# DCDC_Motherbord.net
KiCad netlist of a schematic drawn in Altium Designer
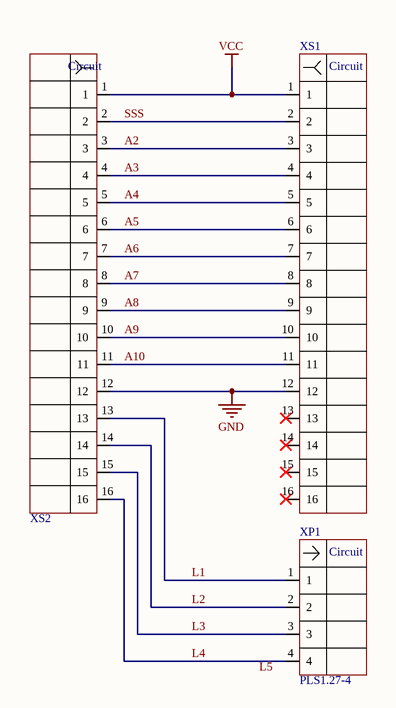
[diagram p0: DCDC_Motherbord.SchDoc]

(export (version "E")
  (design (tool "Eeschema 10.0.6"))
  (components
    (comp (ref "XP1")
      (value "PLS1.27-4")
      (footprint "PLLS1.27-4")
      (libsource (lib "SssAccesDatbase") (part "XP-4"))
    )
    (comp (ref "XS1")
      (value "PBD-16")
      (footprint "PBD-16-3D")
      (description "CONN RCPT 16POS 0.1 GOLD PCB")
      (fields (field (name "PART NUMBER") "SH2-16G") (field (name "DIGI-KEY PART NUMBER") "ED3071-ND"))
      (libsource (lib "") (part "XS-16_1"))
    )
    (comp (ref "XS2")
      (value "PBD-16")
      (footprint "PBD-16-3D")
      (description "CONN RCPT 16POS 0.1 GOLD PCB")
      (fields (field (name "PART NUMBER") "SH2-16G") (field (name "DIGI-KEY PART NUMBER") "ED3071-ND"))
      (libsource (lib "SssAccesDatbase") (part "XS-16"))
    )
  )
  (nets
    (net (code "1") (name "/A2") (class "Default")
      (node (ref "XS1") (pin "3") (pinfunction "3_3") (pintype "passive"))
      (node (ref "XS2") (pin "3") (pinfunction "3_3") (pintype "passive"))
    )
    (net (code "2") (name "/A3") (class "Default")
      (node (ref "XS1") (pin "4") (pinfunction "4_4") (pintype "passive"))
      (node (ref "XS2") (pin "4") (pinfunction "4_4") (pintype "passive"))
    )
    (net (code "3") (name "/A4") (class "Default")
      (node (ref "XS1") (pin "5") (pinfunction "5_5") (pintype "passive"))
      (node (ref "XS2") (pin "5") (pinfunction "5_5") (pintype "passive"))
    )
    (net (code "4") (name "/A5") (class "Default")
      (node (ref "XS1") (pin "6") (pinfunction "6_6") (pintype "passive"))
      (node (ref "XS2") (pin "6") (pinfunction "6_6") (pintype "passive"))
    )
    (net (code "5") (name "/A6") (class "Default")
      (node (ref "XS1") (pin "7") (pinfunction "7_7") (pintype "passive"))
      (node (ref "XS2") (pin "7") (pinfunction "7_7") (pintype "passive"))
    )
    (net (code "6") (name "/A7") (class "Default")
      (node (ref "XS1") (pin "8") (pinfunction "8_8") (pintype "passive"))
      (node (ref "XS2") (pin "8") (pinfunction "8_8") (pintype "passive"))
    )
    (net (code "7") (name "/A8") (class "Default")
      (node (ref "XS1") (pin "9") (pinfunction "9_9") (pintype "passive"))
      (node (ref "XS2") (pin "9") (pinfunction "9_9") (pintype "passive"))
    )
    (net (code "8") (name "/A9") (class "Default")
      (node (ref "XS1") (pin "10") (pinfunction "10_10") (pintype "passive"))
      (node (ref "XS2") (pin "10") (pinfunction "10_10") (pintype "passive"))
    )
    (net (code "9") (name "/A10") (class "Default")
      (node (ref "XS1") (pin "11") (pinfunction "11_11") (pintype "passive"))
      (node (ref "XS2") (pin "11") (pinfunction "11_11") (pintype "passive"))
    )
    (net (code "10") (name "/L1") (class "Default")
      (node (ref "XP1") (pin "1") (pinfunction "1_1") (pintype "passive"))
      (node (ref "XS2") (pin "13") (pinfunction "13_13") (pintype "passive"))
    )
    (net (code "11") (name "/L2") (class "Default")
      (node (ref "XP1") (pin "2") (pinfunction "2_2") (pintype "passive"))
      (node (ref "XS2") (pin "14") (pinfunction "14_14") (pintype "passive"))
    )
    (net (code "12") (name "/L3") (class "Default")
      (node (ref "XP1") (pin "3") (pinfunction "3_3") (pintype "passive"))
      (node (ref "XS2") (pin "15") (pinfunction "15_15") (pintype "passive"))
    )
    (net (code "13") (name "/L4") (class "Default")
      (node (ref "XP1") (pin "4") (pinfunction "4_4") (pintype "passive"))
      (node (ref "XS2") (pin "16") (pinfunction "16_16") (pintype "passive"))
    )
    (net (code "15") (name "/SSS") (class "Default")
      (node (ref "XS1") (pin "2") (pinfunction "2_2") (pintype "passive"))
      (node (ref "XS2") (pin "2") (pinfunction "2_2") (pintype "passive"))
    )
    (net (code "16") (name "GND") (class "Default")
      (node (ref "XS1") (pin "12") (pinfunction "12_12") (pintype "passive"))
      (node (ref "XS2") (pin "12") (pinfunction "12_12") (pintype "passive"))
    )
    (net (code "17") (name "VCC") (class "Default")
      (node (ref "XS1") (pin "1") (pinfunction "1_1") (pintype "passive"))
      (node (ref "XS2") (pin "1") (pinfunction "1_1") (pintype "passive"))
    )
    (net (code "18") (name "unconnected-(XS1-Pad13)") (class "Default")
      (node (ref "XS1") (pin "13") (pinfunction "13_13") (pintype "passive+no_connect"))
    )
    (net (code "19") (name "unconnected-(XS1-Pad14)") (class "Default")
      (node (ref "XS1") (pin "14") (pinfunction "14_14") (pintype "passive+no_connect"))
    )
    (net (code "20") (name "unconnected-(XS1-Pad15)") (class "Default")
      (node (ref "XS1") (pin "15") (pinfunction "15_15") (pintype "passive+no_connect"))
    )
    (net (code "21") (name "unconnected-(XS1-Pad16)") (class "Default")
      (node (ref "XS1") (pin "16") (pinfunction "16_16") (pintype "passive+no_connect"))
    )
  )
)
